# MySXSenors.net
KiCad netlist of a schematic drawn in EAGLE
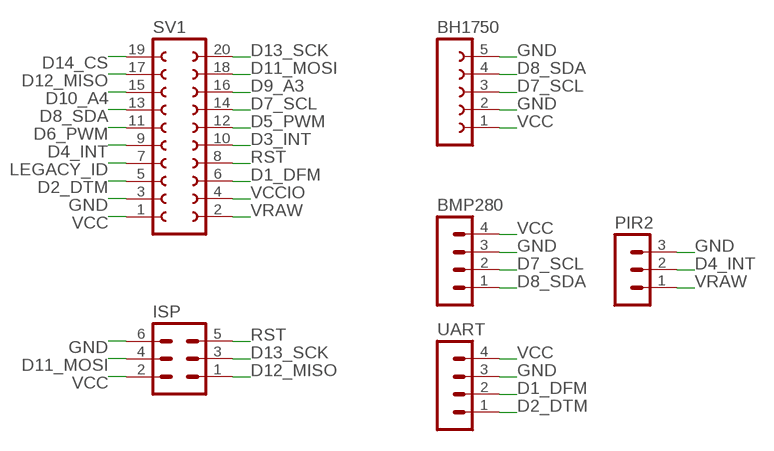
[diagram p0: schematic, sheet 1]

(export (version "E")
  (design (tool "Eeschema 10.0.6"))
  (components
    (comp (ref "BH1750")
      (value "FE05-1")
      (footprint "eagle-import:FE05-1")
      (libsource (lib "eagle-import") (part "FE05-1"))
    )
    (comp (ref "BMP280")
      (value "MA04-1")
      (footprint "eagle-import:MA04-1")
      (libsource (lib "eagle-import") (part "MA04-1"))
    )
    (comp (ref "ISP")
      (value "MA03-2")
      (footprint "eagle-import:MA03-2")
      (libsource (lib "eagle-import") (part "MA03-2"))
    )
    (comp (ref "PIR2")
      (value "MA03-1")
      (footprint "eagle-import:MA03-1")
      (libsource (lib "eagle-import") (part "MA03-1"))
    )
    (comp (ref "SV1")
      (value "FE10-2")
      (footprint "eagle-import:FE10-2")
      (libsource (lib "eagle-import") (part "FE10-2"))
    )
    (comp (ref "UART")
      (value "MA04-1")
      (footprint "eagle-import:MA04-1")
      (libsource (lib "eagle-import") (part "MA04-1"))
    )
  )
  (nets
    (net (code "1") (name "/D1_DFM") (class "Default")
      (node (ref "SV1") (pin "6") (pinfunction "6_6") (pintype "passive"))
      (node (ref "UART") (pin "2") (pinfunction "2_2") (pintype "passive"))
    )
    (net (code "2") (name "/D2_DTM") (class "Default")
      (node (ref "SV1") (pin "5") (pinfunction "5_5") (pintype "passive"))
      (node (ref "UART") (pin "1") (pinfunction "1_1") (pintype "passive"))
    )
    (net (code "3") (name "/D3_INT") (class "Default")
      (node (ref "SV1") (pin "10") (pinfunction "10_10") (pintype "passive"))
    )
    (net (code "4") (name "/D4_INT") (class "Default")
      (node (ref "PIR2") (pin "2") (pinfunction "2_2") (pintype "passive"))
      (node (ref "SV1") (pin "9") (pinfunction "9_9") (pintype "passive"))
    )
    (net (code "5") (name "/D5_PWM") (class "Default")
      (node (ref "SV1") (pin "12") (pinfunction "12_12") (pintype "passive"))
    )
    (net (code "6") (name "/D6_PWM") (class "Default")
      (node (ref "SV1") (pin "11") (pinfunction "11_11") (pintype "passive"))
    )
    (net (code "7") (name "/D7_SCL") (class "Default")
      (node (ref "BH1750") (pin "3") (pinfunction "3_3") (pintype "passive"))
      (node (ref "BMP280") (pin "2") (pinfunction "2_2") (pintype "passive"))
      (node (ref "SV1") (pin "14") (pinfunction "14_14") (pintype "passive"))
    )
    (net (code "8") (name "/D8_SDA") (class "Default")
      (node (ref "BH1750") (pin "4") (pinfunction "4_4") (pintype "passive"))
      (node (ref "BMP280") (pin "1") (pinfunction "1_1") (pintype "passive"))
      (node (ref "SV1") (pin "13") (pinfunction "13_13") (pintype "passive"))
    )
    (net (code "9") (name "/D9_A3") (class "Default")
      (node (ref "SV1") (pin "16") (pinfunction "16_16") (pintype "passive"))
    )
    (net (code "10") (name "/D10_A4") (class "Default")
      (node (ref "SV1") (pin "15") (pinfunction "15_15") (pintype "passive"))
    )
    (net (code "11") (name "/D11_MOSI") (class "Default")
      (node (ref "ISP") (pin "4") (pinfunction "4_4") (pintype "passive"))
      (node (ref "SV1") (pin "18") (pinfunction "18_18") (pintype "passive"))
    )
    (net (code "12") (name "/D12_MISO") (class "Default")
      (node (ref "ISP") (pin "1") (pinfunction "1_1") (pintype "passive"))
      (node (ref "SV1") (pin "17") (pinfunction "17_17") (pintype "passive"))
    )
    (net (code "13") (name "/D13_SCK") (class "Default")
      (node (ref "ISP") (pin "3") (pinfunction "3_3") (pintype "passive"))
      (node (ref "SV1") (pin "20") (pinfunction "20_20") (pintype "passive"))
    )
    (net (code "14") (name "/D14_CS") (class "Default")
      (node (ref "SV1") (pin "19") (pinfunction "19_19") (pintype "passive"))
    )
    (net (code "15") (name "/GND") (class "Default")
      (node (ref "BH1750") (pin "2") (pinfunction "2_2") (pintype "passive"))
      (node (ref "BH1750") (pin "5") (pinfunction "5_5") (pintype "passive"))
      (node (ref "BMP280") (pin "3") (pinfunction "3_3") (pintype "passive"))
      (node (ref "ISP") (pin "6") (pinfunction "6_6") (pintype "passive"))
      (node (ref "PIR2") (pin "3") (pinfunction "3_3") (pintype "passive"))
      (node (ref "SV1") (pin "3") (pinfunction "3_3") (pintype "passive"))
      (node (ref "UART") (pin "3") (pinfunction "3_3") (pintype "passive"))
    )
    (net (code "16") (name "/LEGACY_ID") (class "Default")
      (node (ref "SV1") (pin "7") (pinfunction "7_7") (pintype "passive"))
    )
    (net (code "17") (name "/RST") (class "Default")
      (node (ref "ISP") (pin "5") (pinfunction "5_5") (pintype "passive"))
      (node (ref "SV1") (pin "8") (pinfunction "8_8") (pintype "passive"))
    )
    (net (code "18") (name "/VCC") (class "Default")
      (node (ref "BH1750") (pin "1") (pinfunction "1_1") (pintype "passive"))
      (node (ref "BMP280") (pin "4") (pinfunction "4_4") (pintype "passive"))
      (node (ref "ISP") (pin "2") (pinfunction "2_2") (pintype "passive"))
      (node (ref "SV1") (pin "1") (pinfunction "1_1") (pintype "passive"))
      (node (ref "UART") (pin "4") (pinfunction "4_4") (pintype "passive"))
    )
    (net (code "19") (name "/VCCIO") (class "Default")
      (node (ref "SV1") (pin "4") (pinfunction "4_4") (pintype "passive"))
    )
    (net (code "20") (name "/VRAW") (class "Default")
      (node (ref "PIR2") (pin "1") (pinfunction "1_1") (pintype "passive"))
      (node (ref "SV1") (pin "2") (pinfunction "2_2") (pintype "passive"))
    )
  )
)
